# SOM.net
KiCad netlist of a schematic drawn in Altium Designer
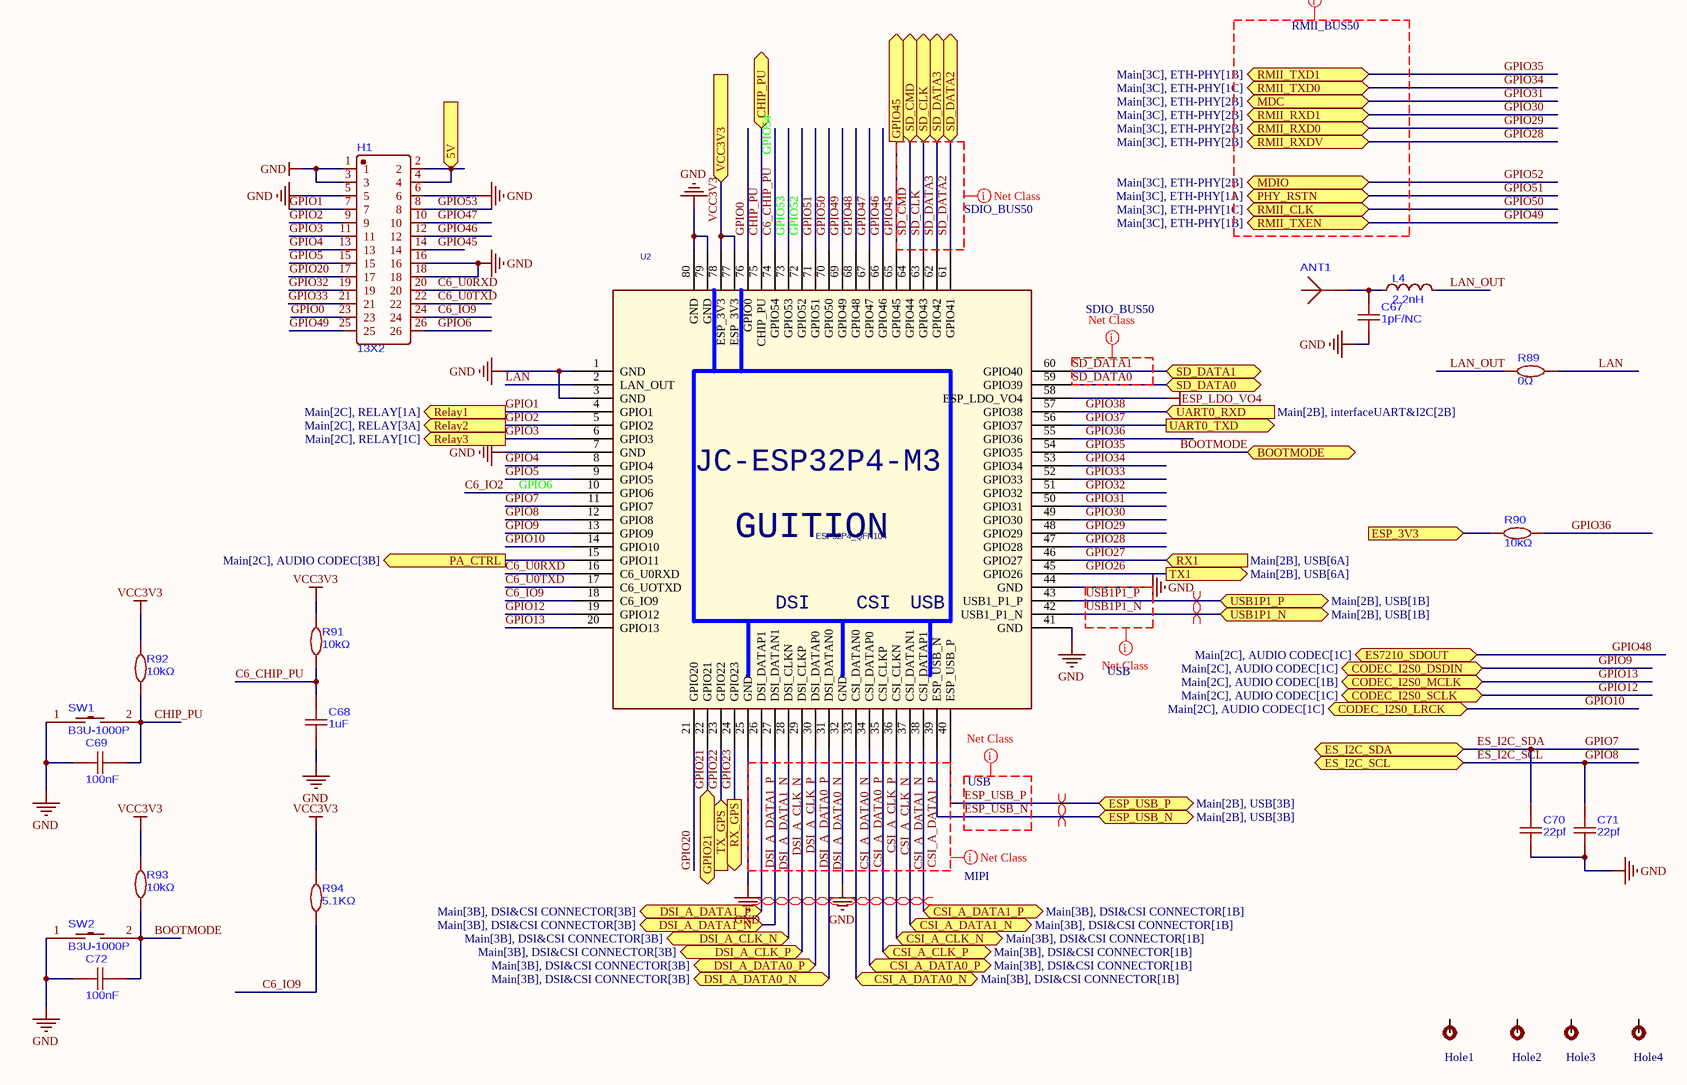
[diagram p0: SOM.SchDoc]

(export (version "E")
  (design (tool "Eeschema 10.0.6"))
  (components
    (comp (ref "ANT1")
      (value "RF ANT 2450MHz CERAMIC SMD")
      (footprint "ANT-SMD-2_L3.2-W1.6-C504002")
      (description "Ceramic Antenna 5.19dBi 100MHz 2.45GHz 1206 RF Antennas RoHS")
      (libsource (lib "Schlib2") (part "kinghelm KH-3216-A35"))
    )
    (comp (ref "C67")
      (value "1pF/NC")
      (footprint "C0603")
      (description "50V 1pF C0G 0603 Ceramic Capacitors RoHS")
      (libsource (lib "Schlib2") (part "FCC0603N1R0C500CT"))
    )
    (comp (ref "C68")
      (value "1uF")
      (footprint "C0603")
      (description "25V 1uF X7R ±10% 0603 Ceramic Capacitors ROHS")
      (libsource (lib "Schlib2") (part "CL10B105KA8NNNC"))
    )
    (comp (ref "C69")
      (value "100nF")
      (footprint "C0603")
      (description "50V 100nF X7R ±10% 0603 Ceramic Capacitors ROHS")
      (libsource (lib "Schlib2") (part "CC0603KRX7R9BB104"))
    )
    (comp (ref "C70")
      (value "22pf")
      (footprint "C0603")
      (description "50V 22pF C0G ±5% 0603 Ceramic Capacitors RoHS")
      (libsource (lib "Schlib2") (part "CL10C220JB8NNNC"))
    )
    (comp (ref "C71")
      (value "22pf")
      (footprint "C0603")
      (description "50V 22pF C0G ±5% 0603 Ceramic Capacitors RoHS")
      (libsource (lib "Schlib2") (part "CL10C220JB8NNNC"))
    )
    (comp (ref "C72")
      (value "100nF")
      (footprint "C0603")
      (description "50V 100nF X7R ±10% 0603 Ceramic Capacitors ROHS")
      (libsource (lib "Schlib2") (part "CC0603KRX7R9BB104"))
    )
    (comp (ref "H1")
      (value "13X2")
      (footprint "HDR-TH_26P-P2.54-V-M-R2-C13-S2.54")
      (libsource (lib "Schlib2") (part "HX PZ2.54-2X13P ZZ"))
    )
    (comp (ref "Hole1")
      (value "Pad Big")
      (footprint "Screw 3.0")
      (libsource (lib "Schlib2") (part "Pad_Big"))
    )
    (comp (ref "Hole2")
      (value "Pad Big")
      (footprint "Screw 3.0")
      (libsource (lib "Schlib2") (part "Pad_Big"))
    )
    (comp (ref "Hole3")
      (value "Pad Big")
      (footprint "Screw 3.0")
      (libsource (lib "Schlib2") (part "Pad_Big"))
    )
    (comp (ref "Hole4")
      (value "Pad Big")
      (footprint "Screw 3.0")
      (libsource (lib "Schlib2") (part "Pad_Big"))
    )
    (comp (ref "L4")
      (value "2.2nH")
      (footprint "C0603")
      (description "700mA 2.2nH ±5% Wirewound Chip Inductor 80mΩ 0603 Fixed Inductors RoHS")
      (libsource (lib "Schlib2") (part "MQG06HF2N2JT7"))
    )
    (comp (ref "R89")
      (value "0Ω")
      (footprint "R0603")
      (description "100mW 0Ω 75V Thick Film Resistor ±5% 0603 Chip Resistor - Surface Mount RoHS")
      (libsource (lib "Schlib2") (part "RC0603JR-070RL"))
    )
    (comp (ref "R90")
      (value "10kΩ")
      (footprint "R0603")
      (description "100mW 10kΩ 75V ±100ppm/℃ Thick Film Resistor ±1% 0603 Chip Resistor - Surface Mount ROHS")
      (libsource (lib "Schlib2") (part "RC0603FR-0710KL"))
    )
    (comp (ref "R91")
      (value "10kΩ")
      (footprint "R0603")
      (description "100mW 10kΩ 75V ±100ppm/℃ Thick Film Resistor ±1% 0603 Chip Resistor - Surface Mount ROHS")
      (libsource (lib "Schlib2") (part "RC0603FR-0710KL"))
    )
    (comp (ref "R92")
      (value "10kΩ")
      (footprint "R0603")
      (description "100mW 10kΩ 75V ±100ppm/℃ Thick Film Resistor ±1% 0603 Chip Resistor - Surface Mount ROHS")
      (libsource (lib "Schlib2") (part "RC0603FR-0710KL"))
    )
    (comp (ref "R93")
      (value "10kΩ")
      (footprint "R0603")
      (description "100mW 10kΩ 75V ±100ppm/℃ Thick Film Resistor ±1% 0603 Chip Resistor - Surface Mount ROHS")
      (libsource (lib "Schlib2") (part "RC0603FR-0710KL"))
    )
    (comp (ref "R94")
      (value "5.1KΩ")
      (footprint "R0603")
      (description "100mW 5.1kΩ 75V ±100ppm/℃ Thick Film Resistor ±1% 0603 Chip Resistor - Surface Mount RoHS")
      (libsource (lib "Schlib2") (part "FRC0603F5101TS"))
    )
    (comp (ref "SW1")
      (value "B3U-1000P")
      (footprint "KEY-SMD_B3U-1000PM")
      (description "12V 2.5mm Round Button 3mm SPST 50mA SMD,3x2.5mm Tactile Switches ROHS")
      (libsource (lib "Schlib2") (part "B3U-1000P"))
    )
    (comp (ref "SW2")
      (value "B3U-1000P")
      (footprint "KEY-SMD_B3U-1000PM")
      (description "12V 2.5mm Round Button 3mm SPST 50mA SMD,3x2.5mm Tactile Switches ROHS")
      (libsource (lib "Schlib2") (part "B3U-1000P"))
    )
    (comp (ref "U2")
      (value "ESP32P4_QFN104")
      (footprint "JC-ESP32P4-M3_V0.2")
      (libsource (lib "Schlib2") (part "JC-ESP32P4-M3"))
    )
  )
  (nets
    (net (code "1") (name "/5V") (class "Default")
      (node (ref "H1") (pin "2") (pinfunction "2_2") (pintype "passive"))
      (node (ref "H1") (pin "4") (pinfunction "4_4") (pintype "passive"))
    )
    (net (code "2") (name "/BOOTMODE") (class "Default")
      (node (ref "C72") (pin "1") (pinfunction "1_1") (pintype "passive"))
      (node (ref "R93") (pin "1") (pinfunction "1_1") (pintype "passive"))
      (node (ref "SW2") (pin "2") (pinfunction "2_2") (pintype "passive"))
      (node (ref "U2") (pin "54") (pinfunction "GPIO35_54") (pintype "passive"))
    )
    (net (code "3") (name "/C6_CHIP_PU") (class "Default")
      (node (ref "C68") (pin "2") (pinfunction "2_2") (pintype "passive"))
      (node (ref "R91") (pin "1") (pinfunction "1_1") (pintype "passive"))
      (node (ref "U2") (pin "74") (pinfunction "GPIO54_74") (pintype "passive"))
    )
    (net (code "4") (name "/C6_IO2") (class "Default")
      (node (ref "H1") (pin "26") (pinfunction "26_26") (pintype "passive"))
      (node (ref "U2") (pin "10") (pinfunction "GPIO6_10") (pintype "passive"))
    )
    (net (code "5") (name "/C6_IO9") (class "Default")
      (node (ref "H1") (pin "24") (pinfunction "24_24") (pintype "passive"))
      (node (ref "R94") (pin "1") (pinfunction "1_1") (pintype "passive"))
      (node (ref "U2") (pin "18") (pinfunction "C6_IO9_18") (pintype "passive"))
    )
    (net (code "6") (name "/C6_U0RXD") (class "Default")
      (node (ref "H1") (pin "20") (pinfunction "20_20") (pintype "passive"))
      (node (ref "U2") (pin "16") (pinfunction "C6_U0RXD_16") (pintype "passive"))
    )
    (net (code "7") (name "/C6_U0TXD") (class "Default")
      (node (ref "H1") (pin "22") (pinfunction "22_22") (pintype "passive"))
      (node (ref "U2") (pin "17") (pinfunction "C6_UOTXD_17") (pintype "passive"))
    )
    (net (code "8") (name "/CHIP_PU") (class "Default")
      (node (ref "C69") (pin "1") (pinfunction "1_1") (pintype "passive"))
      (node (ref "R92") (pin "1") (pinfunction "1_1") (pintype "passive"))
      (node (ref "SW1") (pin "2") (pinfunction "2_2") (pintype "passive"))
      (node (ref "U2") (pin "75") (pinfunction "CHIP_PU_75") (pintype "passive"))
    )
    (net (code "9") (name "/CSI_A_CLK_N") (class "Default")
      (node (ref "U2") (pin "36") (pinfunction "CSI_CLKN_36") (pintype "passive"))
    )
    (net (code "10") (name "/CSI_A_CLK_P") (class "Default")
      (node (ref "U2") (pin "35") (pinfunction "CSI_CLKP_35") (pintype "passive"))
    )
    (net (code "11") (name "/CSI_A_DATA0_N") (class "Default")
      (node (ref "U2") (pin "33") (pinfunction "CSI_DATAN0_33") (pintype "passive"))
    )
    (net (code "12") (name "/CSI_A_DATA0_P") (class "Default")
      (node (ref "U2") (pin "34") (pinfunction "CSI_DATAP0_34") (pintype "passive"))
    )
    (net (code "13") (name "/CSI_A_DATA1_N") (class "Default")
      (node (ref "U2") (pin "37") (pinfunction "CSI_DATAN1_37") (pintype "passive"))
    )
    (net (code "14") (name "/CSI_A_DATA1_P") (class "Default")
      (node (ref "U2") (pin "38") (pinfunction "CSI_DATAP1_38") (pintype "passive"))
    )
    (net (code "15") (name "/DSI_A_CLK_N") (class "Default")
      (node (ref "U2") (pin "28") (pinfunction "DSI_CLKN_28") (pintype "passive"))
    )
    (net (code "16") (name "/DSI_A_CLK_P") (class "Default")
      (node (ref "U2") (pin "29") (pinfunction "DSI_CLKP_29") (pintype "passive"))
    )
    (net (code "17") (name "/DSI_A_DATA0_N") (class "Default")
      (node (ref "U2") (pin "31") (pinfunction "DSI_DATAN0_31") (pintype "passive"))
    )
    (net (code "18") (name "/DSI_A_DATA0_P") (class "Default")
      (node (ref "U2") (pin "30") (pinfunction "DSI_DATAP0_30") (pintype "passive"))
    )
    (net (code "19") (name "/DSI_A_DATA1_N") (class "Default")
      (node (ref "U2") (pin "27") (pinfunction "DSI_DATAN1_27") (pintype "passive"))
    )
    (net (code "20") (name "/DSI_A_DATA1_P") (class "Default")
      (node (ref "U2") (pin "26") (pinfunction "DSI_DATAP1_26") (pintype "passive"))
    )
    (net (code "21") (name "/ESP_3V3") (class "Default")
      (node (ref "R90") (pin "1") (pinfunction "1_1") (pintype "passive"))
    )
    (net (code "22") (name "/ESP_USB_N") (class "Default")
      (node (ref "U2") (pin "39") (pinfunction "ESP_USB_N_39") (pintype "passive"))
    )
    (net (code "23") (name "/ESP_USB_P") (class "Default")
      (node (ref "U2") (pin "40") (pinfunction "ESP_USB_P_40") (pintype "passive"))
    )
    (net (code "24") (name "/ES_I2C_SCL") (class "Default")
      (node (ref "C71") (pin "2") (pinfunction "2_2") (pintype "passive"))
      (node (ref "U2") (pin "12") (pinfunction "GPIO8_12") (pintype "passive"))
    )
    (net (code "25") (name "/ES_I2C_SDA") (class "Default")
      (node (ref "C70") (pin "2") (pinfunction "2_2") (pintype "passive"))
      (node (ref "U2") (pin "11") (pinfunction "GPIO7_11") (pintype "passive"))
    )
    (net (code "26") (name "/GPIO0") (class "Default")
      (node (ref "H1") (pin "23") (pinfunction "23_23") (pintype "passive"))
      (node (ref "U2") (pin "76") (pinfunction "GPIO0_76") (pintype "passive"))
    )
    (net (code "27") (name "/GPIO1") (class "Default")
      (node (ref "H1") (pin "7") (pinfunction "7_7") (pintype "passive"))
      (node (ref "U2") (pin "4") (pinfunction "GPIO1_4") (pintype "passive"))
    )
    (net (code "28") (name "/GPIO2") (class "Default")
      (node (ref "H1") (pin "9") (pinfunction "9_9") (pintype "passive"))
      (node (ref "U2") (pin "5") (pinfunction "GPIO2_5") (pintype "passive"))
    )
    (net (code "29") (name "/GPIO3") (class "Default")
      (node (ref "H1") (pin "11") (pinfunction "11_11") (pintype "passive"))
      (node (ref "U2") (pin "6") (pinfunction "GPIO3_6") (pintype "passive"))
    )
    (net (code "30") (name "/GPIO4") (class "Default")
      (node (ref "H1") (pin "13") (pinfunction "13_13") (pintype "passive"))
      (node (ref "U2") (pin "8") (pinfunction "GPIO4_8") (pintype "passive"))
    )
    (net (code "31") (name "/GPIO5") (class "Default")
      (node (ref "H1") (pin "15") (pinfunction "15_15") (pintype "passive"))
      (node (ref "U2") (pin "9") (pinfunction "GPIO5_9") (pintype "passive"))
    )
    (net (code "32") (name "/GPIO9") (class "Default")
      (node (ref "U2") (pin "13") (pinfunction "GPIO9_13") (pintype "passive"))
    )
    (net (code "33") (name "/GPIO10") (class "Default")
      (node (ref "U2") (pin "14") (pinfunction "GPIO10_14") (pintype "passive"))
    )
    (net (code "34") (name "/GPIO12") (class "Default")
      (node (ref "U2") (pin "19") (pinfunction "GPIO12_19") (pintype "passive"))
    )
    (net (code "35") (name "/GPIO13") (class "Default")
      (node (ref "U2") (pin "20") (pinfunction "GPIO13_20") (pintype "passive"))
    )
    (net (code "36") (name "/GPIO20") (class "Default")
      (node (ref "H1") (pin "17") (pinfunction "17_17") (pintype "passive"))
      (node (ref "U2") (pin "21") (pinfunction "GPIO20_21") (pintype "passive"))
    )
    (net (code "37") (name "/GPIO21") (class "Default")
      (node (ref "U2") (pin "22") (pinfunction "GPIO21_22") (pintype "passive"))
    )
    (net (code "38") (name "/GPIO22") (class "Default")
      (node (ref "U2") (pin "23") (pinfunction "GPIO22_23") (pintype "passive"))
    )
    (net (code "39") (name "/GPIO23") (class "Default")
      (node (ref "U2") (pin "24") (pinfunction "GPIO23_24") (pintype "passive"))
    )
    (net (code "40") (name "/GPIO26") (class "Default")
      (node (ref "U2") (pin "45") (pinfunction "GPIO26_45") (pintype "passive"))
    )
    (net (code "41") (name "/GPIO27") (class "Default")
      (node (ref "U2") (pin "46") (pinfunction "GPIO27_46") (pintype "passive"))
    )
    (net (code "42") (name "/GPIO28") (class "Default")
      (node (ref "U2") (pin "47") (pinfunction "GPIO28_47") (pintype "passive"))
    )
    (net (code "43") (name "/GPIO29") (class "Default")
      (node (ref "U2") (pin "48") (pinfunction "GPIO29_48") (pintype "passive"))
    )
    (net (code "44") (name "/GPIO30") (class "Default")
      (node (ref "U2") (pin "49") (pinfunction "GPIO30_49") (pintype "passive"))
    )
    (net (code "45") (name "/GPIO31") (class "Default")
      (node (ref "U2") (pin "50") (pinfunction "GPIO31_50") (pintype "passive"))
    )
    (net (code "46") (name "/GPIO32") (class "Default")
      (node (ref "H1") (pin "19") (pinfunction "19_19") (pintype "passive"))
      (node (ref "U2") (pin "51") (pinfunction "GPIO32_51") (pintype "passive"))
    )
    (net (code "47") (name "/GPIO33") (class "Default")
      (node (ref "H1") (pin "21") (pinfunction "21_21") (pintype "passive"))
      (node (ref "U2") (pin "52") (pinfunction "GPIO33_52") (pintype "passive"))
    )
    (net (code "48") (name "/GPIO34") (class "Default")
      (node (ref "U2") (pin "53") (pinfunction "GPIO34_53") (pintype "passive"))
    )
    (net (code "49") (name "/GPIO36") (class "Default")
      (node (ref "R90") (pin "2") (pinfunction "2_2") (pintype "passive"))
      (node (ref "U2") (pin "55") (pinfunction "GPIO36_55") (pintype "passive"))
    )
    (net (code "50") (name "/GPIO37") (class "Default")
      (node (ref "U2") (pin "56") (pinfunction "GPIO37_56") (pintype "passive"))
    )
    (net (code "51") (name "/GPIO38") (class "Default")
      (node (ref "U2") (pin "57") (pinfunction "GPIO38_57") (pintype "passive"))
    )
    (net (code "52") (name "/GPIO45") (class "Default")
      (node (ref "H1") (pin "14") (pinfunction "14_14") (pintype "passive"))
      (node (ref "U2") (pin "65") (pinfunction "GPIO45_65") (pintype "passive"))
    )
    (net (code "53") (name "/GPIO46") (class "Default")
      (node (ref "H1") (pin "12") (pinfunction "12_12") (pintype "passive"))
      (node (ref "U2") (pin "66") (pinfunction "GPIO46_66") (pintype "passive"))
    )
    (net (code "54") (name "/GPIO47") (class "Default")
      (node (ref "H1") (pin "10") (pinfunction "10_10") (pintype "passive"))
      (node (ref "U2") (pin "67") (pinfunction "GPIO47_67") (pintype "passive"))
    )
    (net (code "55") (name "/GPIO48") (class "Default")
      (node (ref "U2") (pin "68") (pinfunction "GPIO48_68") (pintype "passive"))
    )
    (net (code "56") (name "/GPIO49") (class "Default")
      (node (ref "H1") (pin "25") (pinfunction "25_25") (pintype "passive"))
      (node (ref "U2") (pin "69") (pinfunction "GPIO49_69") (pintype "passive"))
    )
    (net (code "57") (name "/GPIO50") (class "Default")
      (node (ref "U2") (pin "70") (pinfunction "GPIO50_70") (pintype "passive"))
    )
    (net (code "58") (name "/GPIO51") (class "Default")
      (node (ref "U2") (pin "71") (pinfunction "GPIO51_71") (pintype "passive"))
    )
    (net (code "59") (name "/GPIO52") (class "Default")
      (node (ref "U2") (pin "72") (pinfunction "GPIO52_72") (pintype "passive"))
    )
    (net (code "60") (name "/GPIO53") (class "Default")
      (node (ref "H1") (pin "8") (pinfunction "8_8") (pintype "passive"))
      (node (ref "U2") (pin "73") (pinfunction "GPIO53_73") (pintype "passive"))
    )
    (net (code "61") (name "/LAN") (class "Default")
      (node (ref "R89") (pin "2") (pinfunction "2_2") (pintype "passive"))
      (node (ref "U2") (pin "2") (pinfunction "LAN_OUT_2") (pintype "passive"))
    )
    (net (code "62") (name "/LAN_OUT") (class "Default")
      (node (ref "L4") (pin "2") (pinfunction "2_2") (pintype "passive"))
      (node (ref "R89") (pin "1") (pinfunction "1_1") (pintype "passive"))
    )
    (net (code "63") (name "/PA_CTRL") (class "Default")
      (node (ref "U2") (pin "15") (pinfunction "GPIO11_15") (pintype "passive"))
    )
    (net (code "64") (name "/SD_CLK") (class "Default")
      (node (ref "U2") (pin "63") (pinfunction "GPIO43_63") (pintype "passive"))
    )
    (net (code "65") (name "/SD_CMD") (class "Default")
      (node (ref "U2") (pin "64") (pinfunction "GPIO44_64") (pintype "passive"))
    )
    (net (code "66") (name "/SD_DATA0") (class "Default")
      (node (ref "U2") (pin "59") (pinfunction "GPIO39_59") (pintype "passive"))
    )
    (net (code "67") (name "/SD_DATA1") (class "Default")
      (node (ref "U2") (pin "60") (pinfunction "GPIO40_60") (pintype "passive"))
    )
    (net (code "68") (name "/SD_DATA2") (class "Default")
      (node (ref "U2") (pin "61") (pinfunction "GPIO41_61") (pintype "passive"))
    )
    (net (code "69") (name "/SD_DATA3") (class "Default")
      (node (ref "U2") (pin "62") (pinfunction "GPIO42_62") (pintype "passive"))
    )
    (net (code "70") (name "/USB1P1_N") (class "Default")
      (node (ref "U2") (pin "42") (pinfunction "USB1_P1_N_42") (pintype "passive"))
    )
    (net (code "71") (name "/USB1P1_P") (class "Default")
      (node (ref "U2") (pin "43") (pinfunction "USB1_P1_P_43") (pintype "passive"))
    )
    (net (code "72") (name "ESP_LDO_VO4") (class "Default")
      (node (ref "U2") (pin "58") (pinfunction "ESP_LDO_VO4_58") (pintype "passive"))
    )
    (net (code "73") (name "GND") (class "Default")
      (node (ref "C67") (pin "1") (pinfunction "1_1") (pintype "passive"))
      (node (ref "C68") (pin "1") (pinfunction "1_1") (pintype "passive"))
      (node (ref "C69") (pin "2") (pinfunction "2_2") (pintype "passive"))
      (node (ref "C70") (pin "1") (pinfunction "1_1") (pintype "passive"))
      (node (ref "C71") (pin "1") (pinfunction "1_1") (pintype "passive"))
      (node (ref "C72") (pin "2") (pinfunction "2_2") (pintype "passive"))
      (node (ref "H1") (pin "1") (pinfunction "1_1") (pintype "passive"))
      (node (ref "H1") (pin "16") (pinfunction "16_16") (pintype "passive"))
      (node (ref "H1") (pin "18") (pinfunction "18_18") (pintype "passive"))
      (node (ref "H1") (pin "3") (pinfunction "3_3") (pintype "passive"))
      (node (ref "H1") (pin "5") (pinfunction "5_5") (pintype "passive"))
      (node (ref "H1") (pin "6") (pinfunction "6_6") (pintype "passive"))
      (node (ref "SW1") (pin "1") (pinfunction "1_1") (pintype "passive"))
      (node (ref "SW2") (pin "1") (pinfunction "1_1") (pintype "passive"))
      (node (ref "U2") (pin "1") (pinfunction "GND_1") (pintype "passive"))
      (node (ref "U2") (pin "25") (pinfunction "GND_25") (pintype "passive"))
      (node (ref "U2") (pin "3") (pinfunction "GND_3") (pintype "passive"))
      (node (ref "U2") (pin "32") (pinfunction "GND_32") (pintype "passive"))
      (node (ref "U2") (pin "41") (pinfunction "GND_41") (pintype "passive"))
      (node (ref "U2") (pin "44") (pinfunction "GND_44") (pintype "passive"))
      (node (ref "U2") (pin "7") (pinfunction "GND_7") (pintype "passive"))
      (node (ref "U2") (pin "79") (pinfunction "GND_79") (pintype "passive"))
      (node (ref "U2") (pin "80") (pinfunction "GND_80") (pintype "passive"))
    )
    (net (code "74") (name "Net-(ANT1-Pad2)") (class "Default")
      (node (ref "ANT1") (pin "2") (pinfunction "2_2") (pintype "passive"))
      (node (ref "C67") (pin "2") (pinfunction "2_2") (pintype "passive"))
      (node (ref "L4") (pin "1") (pinfunction "1_1") (pintype "passive"))
    )
    (net (code "75") (name "VCC3V3") (class "Default")
      (node (ref "R91") (pin "2") (pinfunction "2_2") (pintype "passive"))
      (node (ref "R92") (pin "2") (pinfunction "2_2") (pintype "passive"))
      (node (ref "R93") (pin "2") (pinfunction "2_2") (pintype "passive"))
      (node (ref "R94") (pin "2") (pinfunction "2_2") (pintype "passive"))
      (node (ref "U2") (pin "77") (pinfunction "ESP_3V3_77") (pintype "passive"))
      (node (ref "U2") (pin "78") (pinfunction "ESP_3V3_78") (pintype "passive"))
    )
    (net (code "76") (name "unconnected-(ANT1-ANT-Pad1)") (class "Default")
      (node (ref "ANT1") (pin "1") (pinfunction "ANT_1") (pintype "passive"))
    )
    (net (code "77") (name "unconnected-(Hole1-Pad1)") (class "Default")
      (node (ref "Hole1") (pin "1") (pinfunction "1_1") (pintype "passive"))
    )
    (net (code "78") (name "unconnected-(Hole2-Pad1)") (class "Default")
      (node (ref "Hole2") (pin "1") (pinfunction "1_1") (pintype "passive"))
    )
    (net (code "79") (name "unconnected-(Hole3-Pad1)") (class "Default")
      (node (ref "Hole3") (pin "1") (pinfunction "1_1") (pintype "passive"))
    )
    (net (code "80") (name "unconnected-(Hole4-Pad1)") (class "Default")
      (node (ref "Hole4") (pin "1") (pinfunction "1_1") (pintype "passive"))
    )
  )
)
